# pwm-4.net
KiCad netlist of a schematic drawn in EAGLE
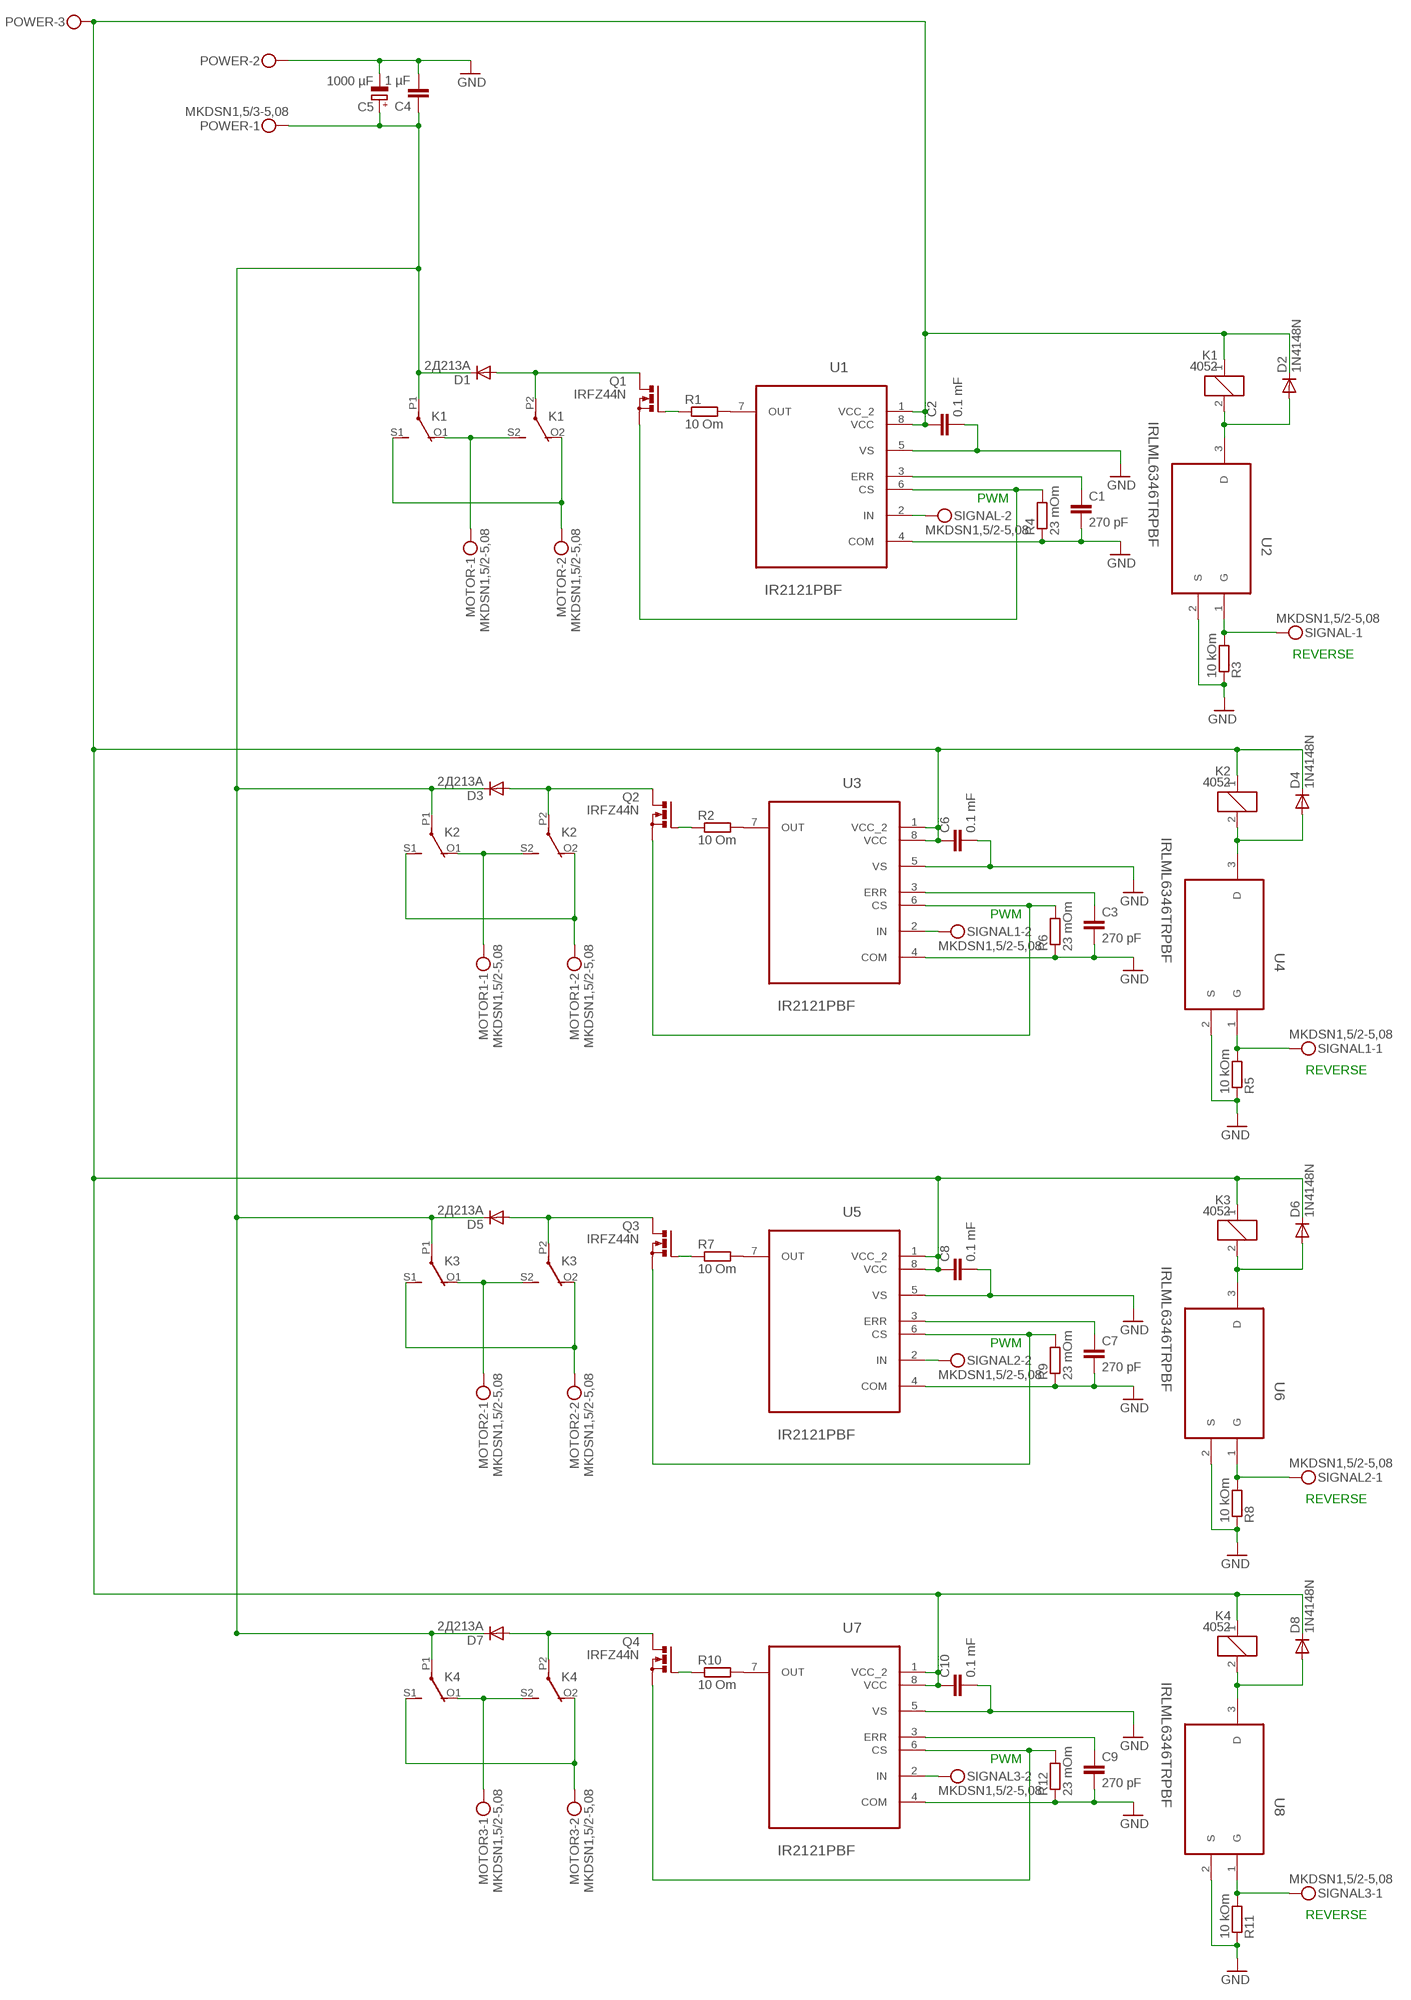
[diagram p0: schematic, sheet 1]

(export (version "E")
  (design (tool "Eeschema 10.0.6"))
  (components
    (comp (ref "C1")
      (value "270 pF")
      (footprint "eagle-import:C025-025X050")
      (libsource (lib "eagle-import") (part "C-EU025-025X050"))
    )
    (comp (ref "C2")
      (value "0.1 mF")
      (footprint "eagle-import:C025-025X050")
      (libsource (lib "eagle-import") (part "C-EU025-025X050"))
    )
    (comp (ref "C3")
      (value "270 pF")
      (footprint "eagle-import:C025-025X050")
      (libsource (lib "eagle-import") (part "C-EU025-025X050"))
    )
    (comp (ref "C4")
      (value "1 µF")
      (footprint "eagle-import:C2.5-3")
      (libsource (lib "eagle-import") (part "C2,5-3"))
    )
    (comp (ref "C5")
      (value "1000 µF")
      (footprint "eagle-import:E7,5-18")
      (libsource (lib "eagle-import") (part "CPOL-EUE7.5-18"))
    )
    (comp (ref "C6")
      (value "0.1 mF")
      (footprint "eagle-import:C025-025X050")
      (libsource (lib "eagle-import") (part "C-EU025-025X050"))
    )
    (comp (ref "C7")
      (value "270 pF")
      (footprint "eagle-import:C025-025X050")
      (libsource (lib "eagle-import") (part "C-EU025-025X050"))
    )
    (comp (ref "C8")
      (value "0.1 mF")
      (footprint "eagle-import:C025-025X050")
      (libsource (lib "eagle-import") (part "C-EU025-025X050"))
    )
    (comp (ref "C9")
      (value "270 pF")
      (footprint "eagle-import:C025-025X050")
      (libsource (lib "eagle-import") (part "C-EU025-025X050"))
    )
    (comp (ref "C10")
      (value "0.1 mF")
      (footprint "eagle-import:C025-025X050")
      (libsource (lib "eagle-import") (part "C-EU025-025X050"))
    )
    (comp (ref "D1")
      (value "2Д213А")
      (footprint "eagle-import:C1702-05")
      (libsource (lib "eagle-import") (part "DIODE-C1702-05"))
    )
    (comp (ref "D2")
      (value "1N4148N")
      (footprint "eagle-import:D-2.5")
      (libsource (lib "eagle-import") (part "DIODE-D-2.5"))
    )
    (comp (ref "D3")
      (value "2Д213А")
      (footprint "eagle-import:C1702-05")
      (libsource (lib "eagle-import") (part "DIODE-C1702-05"))
    )
    (comp (ref "D4")
      (value "1N4148N")
      (footprint "eagle-import:D-2.5")
      (libsource (lib "eagle-import") (part "DIODE-D-2.5"))
    )
    (comp (ref "D5")
      (value "2Д213А")
      (footprint "eagle-import:C1702-05")
      (libsource (lib "eagle-import") (part "DIODE-C1702-05"))
    )
    (comp (ref "D6")
      (value "1N4148N")
      (footprint "eagle-import:D-2.5")
      (libsource (lib "eagle-import") (part "DIODE-D-2.5"))
    )
    (comp (ref "D7")
      (value "2Д213А")
      (footprint "eagle-import:C1702-05")
      (libsource (lib "eagle-import") (part "DIODE-C1702-05"))
    )
    (comp (ref "D8")
      (value "1N4148N")
      (footprint "eagle-import:D-2.5")
      (libsource (lib "eagle-import") (part "DIODE-D-2.5"))
    )
    (comp (ref "K1")
      (value "4052")
      (footprint "eagle-import:F4052")
      (libsource (lib "eagle-import") (part "4052"))
    )
    (comp (ref "K2")
      (value "4052")
      (footprint "eagle-import:F4052")
      (libsource (lib "eagle-import") (part "4052"))
    )
    (comp (ref "K3")
      (value "4052")
      (footprint "eagle-import:F4052")
      (libsource (lib "eagle-import") (part "4052"))
    )
    (comp (ref "K4")
      (value "4052")
      (footprint "eagle-import:F4052")
      (libsource (lib "eagle-import") (part "4052"))
    )
    (comp (ref "MOTOR")
      (value "MKDSN1,5/2-5,08")
      (footprint "eagle-import:MKDSN1,5_2-5,08")
      (fields (field (name "MPN") "MKDSN 1,5/2-5.08"))
      (libsource (lib "eagle-import") (part "MKDSN1,5/2-5,08"))
    )
    (comp (ref "MOTOR1")
      (value "MKDSN1,5/2-5,08")
      (footprint "eagle-import:MKDSN1,5_2-5,08")
      (fields (field (name "MPN") "MKDSN 1,5/2-5.08"))
      (libsource (lib "eagle-import") (part "MKDSN1,5/2-5,08"))
    )
    (comp (ref "MOTOR2")
      (value "MKDSN1,5/2-5,08")
      (footprint "eagle-import:MKDSN1,5_2-5,08")
      (fields (field (name "MPN") "MKDSN 1,5/2-5.08"))
      (libsource (lib "eagle-import") (part "MKDSN1,5/2-5,08"))
    )
    (comp (ref "MOTOR3")
      (value "MKDSN1,5/2-5,08")
      (footprint "eagle-import:MKDSN1,5_2-5,08")
      (fields (field (name "MPN") "MKDSN 1,5/2-5.08"))
      (libsource (lib "eagle-import") (part "MKDSN1,5/2-5,08"))
    )
    (comp (ref "POWER")
      (value "MKDSN1,5/3-5,08")
      (footprint "eagle-import:MKDSN1,5_3-5,08")
      (fields (field (name "MPN") "SMKDSN1,5/3-5,08"))
      (libsource (lib "eagle-import") (part "MKDSN1,5/3-5,08"))
    )
    (comp (ref "Q1")
      (value "IRFZ44N")
      (footprint "eagle-import:TO220BV")
      (libsource (lib "eagle-import") (part "PMOSFET_NTO220BV"))
    )
    (comp (ref "Q2")
      (value "IRFZ44N")
      (footprint "eagle-import:TO220BV")
      (libsource (lib "eagle-import") (part "PMOSFET_NTO220BV"))
    )
    (comp (ref "Q3")
      (value "IRFZ44N")
      (footprint "eagle-import:TO220BV")
      (libsource (lib "eagle-import") (part "PMOSFET_NTO220BV"))
    )
    (comp (ref "Q4")
      (value "IRFZ44N")
      (footprint "eagle-import:TO220BV")
      (libsource (lib "eagle-import") (part "PMOSFET_NTO220BV"))
    )
    (comp (ref "R1")
      (value "10 Om")
      (footprint "eagle-import:0204_5")
      (libsource (lib "eagle-import") (part "R-EU_0204/5"))
    )
    (comp (ref "R2")
      (value "10 Om")
      (footprint "eagle-import:0204_5")
      (libsource (lib "eagle-import") (part "R-EU_0204/5"))
    )
    (comp (ref "R3")
      (value "10 kOm")
      (footprint "eagle-import:0204_5")
      (libsource (lib "eagle-import") (part "R-EU_0204/5"))
    )
    (comp (ref "R4")
      (value "23 mOm")
      (footprint "eagle-import:0204_5")
      (libsource (lib "eagle-import") (part "R-EU_0204/5"))
    )
    (comp (ref "R5")
      (value "10 kOm")
      (footprint "eagle-import:0204_5")
      (libsource (lib "eagle-import") (part "R-EU_0204/5"))
    )
    (comp (ref "R6")
      (value "23 mOm")
      (footprint "eagle-import:0204_5")
      (libsource (lib "eagle-import") (part "R-EU_0204/5"))
    )
    (comp (ref "R7")
      (value "10 Om")
      (footprint "eagle-import:0204_5")
      (libsource (lib "eagle-import") (part "R-EU_0204/5"))
    )
    (comp (ref "R8")
      (value "10 kOm")
      (footprint "eagle-import:0204_5")
      (libsource (lib "eagle-import") (part "R-EU_0204/5"))
    )
    (comp (ref "R9")
      (value "23 mOm")
      (footprint "eagle-import:0204_5")
      (libsource (lib "eagle-import") (part "R-EU_0204/5"))
    )
    (comp (ref "R10")
      (value "10 Om")
      (footprint "eagle-import:0204_5")
      (libsource (lib "eagle-import") (part "R-EU_0204/5"))
    )
    (comp (ref "R11")
      (value "10 kOm")
      (footprint "eagle-import:0204_5")
      (libsource (lib "eagle-import") (part "R-EU_0204/5"))
    )
    (comp (ref "R12")
      (value "23 mOm")
      (footprint "eagle-import:0204_5")
      (libsource (lib "eagle-import") (part "R-EU_0204/5"))
    )
    (comp (ref "SIGNAL")
      (value "MKDSN1,5/2-5,08")
      (footprint "eagle-import:MKDSN1,5_2-5,08")
      (fields (field (name "MPN") "MKDSN 1,5/2-5.08"))
      (libsource (lib "eagle-import") (part "MKDSN1,5/2-5,08"))
    )
    (comp (ref "SIGNAL1")
      (value "MKDSN1,5/2-5,08")
      (footprint "eagle-import:MKDSN1,5_2-5,08")
      (fields (field (name "MPN") "MKDSN 1,5/2-5.08"))
      (libsource (lib "eagle-import") (part "MKDSN1,5/2-5,08"))
    )
    (comp (ref "SIGNAL2")
      (value "MKDSN1,5/2-5,08")
      (footprint "eagle-import:MKDSN1,5_2-5,08")
      (fields (field (name "MPN") "MKDSN 1,5/2-5.08"))
      (libsource (lib "eagle-import") (part "MKDSN1,5/2-5,08"))
    )
    (comp (ref "SIGNAL3")
      (value "MKDSN1,5/2-5,08")
      (footprint "eagle-import:MKDSN1,5_2-5,08")
      (fields (field (name "MPN") "MKDSN 1,5/2-5.08"))
      (libsource (lib "eagle-import") (part "MKDSN1,5/2-5,08"))
    )
    (comp (ref "U1")
      (value "IR2121PBF")
      (footprint "eagle-import:DIP254P762X533-8")
      (libsource (lib "eagle-import") (part "IR2121PBF"))
    )
    (comp (ref "U2")
      (value "IRLML6346TRPBF")
      (footprint "eagle-import:SOT95P240X112-3N")
      (libsource (lib "eagle-import") (part "IRLML6346TRPBF"))
    )
    (comp (ref "U3")
      (value "IR2121PBF")
      (footprint "eagle-import:DIP254P762X533-8")
      (libsource (lib "eagle-import") (part "IR2121PBF"))
    )
    (comp (ref "U4")
      (value "IRLML6346TRPBF")
      (footprint "eagle-import:SOT95P240X112-3N")
      (libsource (lib "eagle-import") (part "IRLML6346TRPBF"))
    )
    (comp (ref "U5")
      (value "IR2121PBF")
      (footprint "eagle-import:DIP254P762X533-8")
      (libsource (lib "eagle-import") (part "IR2121PBF"))
    )
    (comp (ref "U6")
      (value "IRLML6346TRPBF")
      (footprint "eagle-import:SOT95P240X112-3N")
      (libsource (lib "eagle-import") (part "IRLML6346TRPBF"))
    )
    (comp (ref "U7")
      (value "IR2121PBF")
      (footprint "eagle-import:DIP254P762X533-8")
      (libsource (lib "eagle-import") (part "IR2121PBF"))
    )
    (comp (ref "U8")
      (value "IRLML6346TRPBF")
      (footprint "eagle-import:SOT95P240X112-3N")
      (libsource (lib "eagle-import") (part "IRLML6346TRPBF"))
    )
  )
  (nets
    (net (code "1") (name "GND") (class "Default")
      (node (ref "C1") (pin "2") (pinfunction "2_2") (pintype "passive"))
      (node (ref "C10") (pin "2") (pinfunction "2_2") (pintype "passive"))
      (node (ref "C2") (pin "2") (pinfunction "2_2") (pintype "passive"))
      (node (ref "C3") (pin "2") (pinfunction "2_2") (pintype "passive"))
      (node (ref "C4") (pin "2") (pinfunction "2_2") (pintype "passive"))
      (node (ref "C5") (pin "-") (pinfunction "-_-") (pintype "passive"))
      (node (ref "C6") (pin "2") (pinfunction "2_2") (pintype "passive"))
      (node (ref "C7") (pin "2") (pinfunction "2_2") (pintype "passive"))
      (node (ref "C8") (pin "2") (pinfunction "2_2") (pintype "passive"))
      (node (ref "C9") (pin "2") (pinfunction "2_2") (pintype "passive"))
      (node (ref "POWER") (pin "2") (pinfunction "KL_2") (pintype "passive"))
      (node (ref "R11") (pin "1") (pinfunction "1_1") (pintype "passive"))
      (node (ref "R12") (pin "1") (pinfunction "1_1") (pintype "passive"))
      (node (ref "R3") (pin "1") (pinfunction "1_1") (pintype "passive"))
      (node (ref "R4") (pin "1") (pinfunction "1_1") (pintype "passive"))
      (node (ref "R5") (pin "1") (pinfunction "1_1") (pintype "passive"))
      (node (ref "R6") (pin "1") (pinfunction "1_1") (pintype "passive"))
      (node (ref "R8") (pin "1") (pinfunction "1_1") (pintype "passive"))
      (node (ref "R9") (pin "1") (pinfunction "1_1") (pintype "passive"))
      (node (ref "U1") (pin "4") (pinfunction "COM_4") (pintype "passive"))
      (node (ref "U1") (pin "5") (pinfunction "VS_5") (pintype "power_in"))
      (node (ref "U2") (pin "2") (pinfunction "S_2") (pintype "passive"))
      (node (ref "U3") (pin "4") (pinfunction "COM_4") (pintype "passive"))
      (node (ref "U3") (pin "5") (pinfunction "VS_5") (pintype "power_in"))
      (node (ref "U4") (pin "2") (pinfunction "S_2") (pintype "passive"))
      (node (ref "U5") (pin "4") (pinfunction "COM_4") (pintype "passive"))
      (node (ref "U5") (pin "5") (pinfunction "VS_5") (pintype "power_in"))
      (node (ref "U6") (pin "2") (pinfunction "S_2") (pintype "passive"))
      (node (ref "U7") (pin "4") (pinfunction "COM_4") (pintype "passive"))
      (node (ref "U7") (pin "5") (pinfunction "VS_5") (pintype "power_in"))
      (node (ref "U8") (pin "2") (pinfunction "S_2") (pintype "passive"))
    )
    (net (code "2") (name "Net-(K1B-O)") (class "Default")
      (node (ref "K1") (pin "O1") (pinfunction "O_O1") (pintype "passive"))
      (node (ref "K1") (pin "S2") (pinfunction "S_S2") (pintype "passive"))
      (node (ref "MOTOR") (pin "1") (pinfunction "KL_1") (pintype "passive"))
    )
    (net (code "3") (name "Net-(K1B-P)") (class "Default")
      (node (ref "C4") (pin "1") (pinfunction "1_1") (pintype "passive"))
      (node (ref "C5") (pin "+") (pinfunction "+_+") (pintype "passive"))
      (node (ref "D1") (pin "C") (pinfunction "C_C") (pintype "passive"))
      (node (ref "D3") (pin "C") (pinfunction "C_C") (pintype "passive"))
      (node (ref "D5") (pin "C") (pinfunction "C_C") (pintype "passive"))
      (node (ref "D7") (pin "C") (pinfunction "C_C") (pintype "passive"))
      (node (ref "K1") (pin "P1") (pinfunction "P_P1") (pintype "passive"))
      (node (ref "K2") (pin "P1") (pinfunction "P_P1") (pintype "passive"))
      (node (ref "K3") (pin "P1") (pinfunction "P_P1") (pintype "passive"))
      (node (ref "K4") (pin "P1") (pinfunction "P_P1") (pintype "passive"))
      (node (ref "POWER") (pin "1") (pinfunction "KL_1") (pintype "passive"))
    )
    (net (code "4") (name "Net-(K1B-S)") (class "Default")
      (node (ref "K1") (pin "O2") (pinfunction "O_O2") (pintype "passive"))
      (node (ref "K1") (pin "S1") (pinfunction "S_S1") (pintype "passive"))
      (node (ref "MOTOR") (pin "2") (pinfunction "KL_2") (pintype "passive"))
    )
    (net (code "5") (name "Net-(K1C-P)") (class "Default")
      (node (ref "D1") (pin "A") (pinfunction "A_A") (pintype "passive"))
      (node (ref "K1") (pin "P2") (pinfunction "P_P2") (pintype "passive"))
      (node (ref "Q1") (pin "D") (pinfunction "D_D") (pintype "passive"))
    )
    (net (code "6") (name "Net-(K2B-O)") (class "Default")
      (node (ref "K2") (pin "O1") (pinfunction "O_O1") (pintype "passive"))
      (node (ref "K2") (pin "S2") (pinfunction "S_S2") (pintype "passive"))
      (node (ref "MOTOR1") (pin "1") (pinfunction "KL_1") (pintype "passive"))
    )
    (net (code "7") (name "Net-(K2B-S)") (class "Default")
      (node (ref "K2") (pin "O2") (pinfunction "O_O2") (pintype "passive"))
      (node (ref "K2") (pin "S1") (pinfunction "S_S1") (pintype "passive"))
      (node (ref "MOTOR1") (pin "2") (pinfunction "KL_2") (pintype "passive"))
    )
    (net (code "8") (name "Net-(K2C-P)") (class "Default")
      (node (ref "D3") (pin "A") (pinfunction "A_A") (pintype "passive"))
      (node (ref "K2") (pin "P2") (pinfunction "P_P2") (pintype "passive"))
      (node (ref "Q2") (pin "D") (pinfunction "D_D") (pintype "passive"))
    )
    (net (code "9") (name "Net-(K3B-O)") (class "Default")
      (node (ref "K3") (pin "O1") (pinfunction "O_O1") (pintype "passive"))
      (node (ref "K3") (pin "S2") (pinfunction "S_S2") (pintype "passive"))
      (node (ref "MOTOR2") (pin "1") (pinfunction "KL_1") (pintype "passive"))
    )
    (net (code "10") (name "Net-(K3B-S)") (class "Default")
      (node (ref "K3") (pin "O2") (pinfunction "O_O2") (pintype "passive"))
      (node (ref "K3") (pin "S1") (pinfunction "S_S1") (pintype "passive"))
      (node (ref "MOTOR2") (pin "2") (pinfunction "KL_2") (pintype "passive"))
    )
    (net (code "11") (name "Net-(K3C-P)") (class "Default")
      (node (ref "D5") (pin "A") (pinfunction "A_A") (pintype "passive"))
      (node (ref "K3") (pin "P2") (pinfunction "P_P2") (pintype "passive"))
      (node (ref "Q3") (pin "D") (pinfunction "D_D") (pintype "passive"))
    )
    (net (code "12") (name "Net-(K4B-O)") (class "Default")
      (node (ref "K4") (pin "O1") (pinfunction "O_O1") (pintype "passive"))
      (node (ref "K4") (pin "S2") (pinfunction "S_S2") (pintype "passive"))
      (node (ref "MOTOR3") (pin "1") (pinfunction "KL_1") (pintype "passive"))
    )
    (net (code "13") (name "Net-(K4B-S)") (class "Default")
      (node (ref "K4") (pin "O2") (pinfunction "O_O2") (pintype "passive"))
      (node (ref "K4") (pin "S1") (pinfunction "S_S1") (pintype "passive"))
      (node (ref "MOTOR3") (pin "2") (pinfunction "KL_2") (pintype "passive"))
    )
    (net (code "14") (name "Net-(K4C-P)") (class "Default")
      (node (ref "D7") (pin "A") (pinfunction "A_A") (pintype "passive"))
      (node (ref "K4") (pin "P2") (pinfunction "P_P2") (pintype "passive"))
      (node (ref "Q4") (pin "D") (pinfunction "D_D") (pintype "passive"))
    )
    (net (code "15") (name "Net-(POWERC-KL)") (class "Default")
      (node (ref "C10") (pin "1") (pinfunction "1_1") (pintype "passive"))
      (node (ref "C2") (pin "1") (pinfunction "1_1") (pintype "passive"))
      (node (ref "C6") (pin "1") (pinfunction "1_1") (pintype "passive"))
      (node (ref "C8") (pin "1") (pinfunction "1_1") (pintype "passive"))
      (node (ref "D2") (pin "C") (pinfunction "C_C") (pintype "passive"))
      (node (ref "D4") (pin "C") (pinfunction "C_C") (pintype "passive"))
      (node (ref "D6") (pin "C") (pinfunction "C_C") (pintype "passive"))
      (node (ref "D8") (pin "C") (pinfunction "C_C") (pintype "passive"))
      (node (ref "K1") (pin "1") (pinfunction "1_1") (pintype "passive"))
      (node (ref "K2") (pin "1") (pinfunction "1_1") (pintype "passive"))
      (node (ref "K3") (pin "1") (pinfunction "1_1") (pintype "passive"))
      (node (ref "K4") (pin "1") (pinfunction "1_1") (pintype "passive"))
      (node (ref "POWER") (pin "3") (pinfunction "KL_3") (pintype "passive"))
      (node (ref "U1") (pin "1") (pinfunction "VCC_2_1") (pintype "power_in"))
      (node (ref "U1") (pin "8") (pinfunction "VCC_8") (pintype "power_in"))
      (node (ref "U3") (pin "1") (pinfunction "VCC_2_1") (pintype "power_in"))
      (node (ref "U3") (pin "8") (pinfunction "VCC_8") (pintype "power_in"))
      (node (ref "U5") (pin "1") (pinfunction "VCC_2_1") (pintype "power_in"))
      (node (ref "U5") (pin "8") (pinfunction "VCC_8") (pintype "power_in"))
      (node (ref "U7") (pin "1") (pinfunction "VCC_2_1") (pintype "power_in"))
      (node (ref "U7") (pin "8") (pinfunction "VCC_8") (pintype "power_in"))
    )
    (net (code "16") (name "Net-(Q1-PadG)") (class "Default")
      (node (ref "Q1") (pin "G") (pinfunction "G_G") (pintype "passive"))
      (node (ref "R1") (pin "1") (pinfunction "1_1") (pintype "passive"))
    )
    (net (code "17") (name "Net-(Q2-PadG)") (class "Default")
      (node (ref "Q2") (pin "G") (pinfunction "G_G") (pintype "passive"))
      (node (ref "R2") (pin "1") (pinfunction "1_1") (pintype "passive"))
    )
    (net (code "18") (name "Net-(Q3-PadG)") (class "Default")
      (node (ref "Q3") (pin "G") (pinfunction "G_G") (pintype "passive"))
      (node (ref "R7") (pin "1") (pinfunction "1_1") (pintype "passive"))
    )
    (net (code "19") (name "Net-(Q4-PadG)") (class "Default")
      (node (ref "Q4") (pin "G") (pinfunction "G_G") (pintype "passive"))
      (node (ref "R10") (pin "1") (pinfunction "1_1") (pintype "passive"))
    )
    (net (code "20") (name "Net-(SIGNAL1A-KL)") (class "Default")
      (node (ref "R5") (pin "2") (pinfunction "2_2") (pintype "passive"))
      (node (ref "SIGNAL1") (pin "1") (pinfunction "KL_1") (pintype "passive"))
      (node (ref "U4") (pin "1") (pinfunction "G_1") (pintype "input"))
    )
    (net (code "21") (name "Net-(SIGNAL1B-KL)") (class "Default")
      (node (ref "SIGNAL1") (pin "2") (pinfunction "KL_2") (pintype "passive"))
      (node (ref "U3") (pin "2") (pinfunction "IN_2") (pintype "input"))
    )
    (net (code "22") (name "Net-(SIGNAL2A-KL)") (class "Default")
      (node (ref "R8") (pin "2") (pinfunction "2_2") (pintype "passive"))
      (node (ref "SIGNAL2") (pin "1") (pinfunction "KL_1") (pintype "passive"))
      (node (ref "U6") (pin "1") (pinfunction "G_1") (pintype "input"))
    )
    (net (code "23") (name "Net-(SIGNAL2B-KL)") (class "Default")
      (node (ref "SIGNAL2") (pin "2") (pinfunction "KL_2") (pintype "passive"))
      (node (ref "U5") (pin "2") (pinfunction "IN_2") (pintype "input"))
    )
    (net (code "24") (name "Net-(SIGNAL3A-KL)") (class "Default")
      (node (ref "R11") (pin "2") (pinfunction "2_2") (pintype "passive"))
      (node (ref "SIGNAL3") (pin "1") (pinfunction "KL_1") (pintype "passive"))
      (node (ref "U8") (pin "1") (pinfunction "G_1") (pintype "input"))
    )
    (net (code "25") (name "Net-(SIGNAL3B-KL)") (class "Default")
      (node (ref "SIGNAL3") (pin "2") (pinfunction "KL_2") (pintype "passive"))
      (node (ref "U7") (pin "2") (pinfunction "IN_2") (pintype "input"))
    )
    (net (code "26") (name "Net-(SIGNALA-KL)") (class "Default")
      (node (ref "R3") (pin "2") (pinfunction "2_2") (pintype "passive"))
      (node (ref "SIGNAL") (pin "1") (pinfunction "KL_1") (pintype "passive"))
      (node (ref "U2") (pin "1") (pinfunction "G_1") (pintype "input"))
    )
    (net (code "27") (name "Net-(SIGNALB-KL)") (class "Default")
      (node (ref "SIGNAL") (pin "2") (pinfunction "KL_2") (pintype "passive"))
      (node (ref "U1") (pin "2") (pinfunction "IN_2") (pintype "input"))
    )
    (net (code "28") (name "Net-(U1-CS)") (class "Default")
      (node (ref "Q1") (pin "S") (pinfunction "S_S") (pintype "passive"))
      (node (ref "R4") (pin "2") (pinfunction "2_2") (pintype "passive"))
      (node (ref "U1") (pin "6") (pinfunction "CS_6") (pintype "passive"))
    )
    (net (code "29") (name "Net-(U1-ERR)") (class "Default")
      (node (ref "C1") (pin "1") (pinfunction "1_1") (pintype "passive"))
      (node (ref "U1") (pin "3") (pinfunction "ERR_3") (pintype "input"))
    )
    (net (code "30") (name "Net-(U1-OUT)") (class "Default")
      (node (ref "R1") (pin "2") (pinfunction "2_2") (pintype "passive"))
      (node (ref "U1") (pin "7") (pinfunction "OUT_7") (pintype "output"))
    )
    (net (code "31") (name "Net-(U2-D)") (class "Default")
      (node (ref "D2") (pin "A") (pinfunction "A_A") (pintype "passive"))
      (node (ref "K1") (pin "2") (pinfunction "2_2") (pintype "passive"))
      (node (ref "U2") (pin "3") (pinfunction "D_3") (pintype "output"))
    )
    (net (code "32") (name "Net-(U3-CS)") (class "Default")
      (node (ref "Q2") (pin "S") (pinfunction "S_S") (pintype "passive"))
      (node (ref "R6") (pin "2") (pinfunction "2_2") (pintype "passive"))
      (node (ref "U3") (pin "6") (pinfunction "CS_6") (pintype "passive"))
    )
    (net (code "33") (name "Net-(U3-ERR)") (class "Default")
      (node (ref "C3") (pin "1") (pinfunction "1_1") (pintype "passive"))
      (node (ref "U3") (pin "3") (pinfunction "ERR_3") (pintype "input"))
    )
    (net (code "34") (name "Net-(U3-OUT)") (class "Default")
      (node (ref "R2") (pin "2") (pinfunction "2_2") (pintype "passive"))
      (node (ref "U3") (pin "7") (pinfunction "OUT_7") (pintype "output"))
    )
    (net (code "35") (name "Net-(U4-D)") (class "Default")
      (node (ref "D4") (pin "A") (pinfunction "A_A") (pintype "passive"))
      (node (ref "K2") (pin "2") (pinfunction "2_2") (pintype "passive"))
      (node (ref "U4") (pin "3") (pinfunction "D_3") (pintype "output"))
    )
    (net (code "36") (name "Net-(U5-CS)") (class "Default")
      (node (ref "Q3") (pin "S") (pinfunction "S_S") (pintype "passive"))
      (node (ref "R9") (pin "2") (pinfunction "2_2") (pintype "passive"))
      (node (ref "U5") (pin "6") (pinfunction "CS_6") (pintype "passive"))
    )
    (net (code "37") (name "Net-(U5-ERR)") (class "Default")
      (node (ref "C7") (pin "1") (pinfunction "1_1") (pintype "passive"))
      (node (ref "U5") (pin "3") (pinfunction "ERR_3") (pintype "input"))
    )
    (net (code "38") (name "Net-(U5-OUT)") (class "Default")
      (node (ref "R7") (pin "2") (pinfunction "2_2") (pintype "passive"))
      (node (ref "U5") (pin "7") (pinfunction "OUT_7") (pintype "output"))
    )
    (net (code "39") (name "Net-(U6-D)") (class "Default")
      (node (ref "D6") (pin "A") (pinfunction "A_A") (pintype "passive"))
      (node (ref "K3") (pin "2") (pinfunction "2_2") (pintype "passive"))
      (node (ref "U6") (pin "3") (pinfunction "D_3") (pintype "output"))
    )
    (net (code "40") (name "Net-(U7-CS)") (class "Default")
      (node (ref "Q4") (pin "S") (pinfunction "S_S") (pintype "passive"))
      (node (ref "R12") (pin "2") (pinfunction "2_2") (pintype "passive"))
      (node (ref "U7") (pin "6") (pinfunction "CS_6") (pintype "passive"))
    )
    (net (code "41") (name "Net-(U7-ERR)") (class "Default")
      (node (ref "C9") (pin "1") (pinfunction "1_1") (pintype "passive"))
      (node (ref "U7") (pin "3") (pinfunction "ERR_3") (pintype "input"))
    )
    (net (code "42") (name "Net-(U7-OUT)") (class "Default")
      (node (ref "R10") (pin "2") (pinfunction "2_2") (pintype "passive"))
      (node (ref "U7") (pin "7") (pinfunction "OUT_7") (pintype "output"))
    )
    (net (code "43") (name "Net-(U8-D)") (class "Default")
      (node (ref "D8") (pin "A") (pinfunction "A_A") (pintype "passive"))
      (node (ref "K4") (pin "2") (pinfunction "2_2") (pintype "passive"))
      (node (ref "U8") (pin "3") (pinfunction "D_3") (pintype "output"))
    )
  )
)
